# USB_SWITCH.net
KiCad netlist of a schematic drawn in Altium Designer
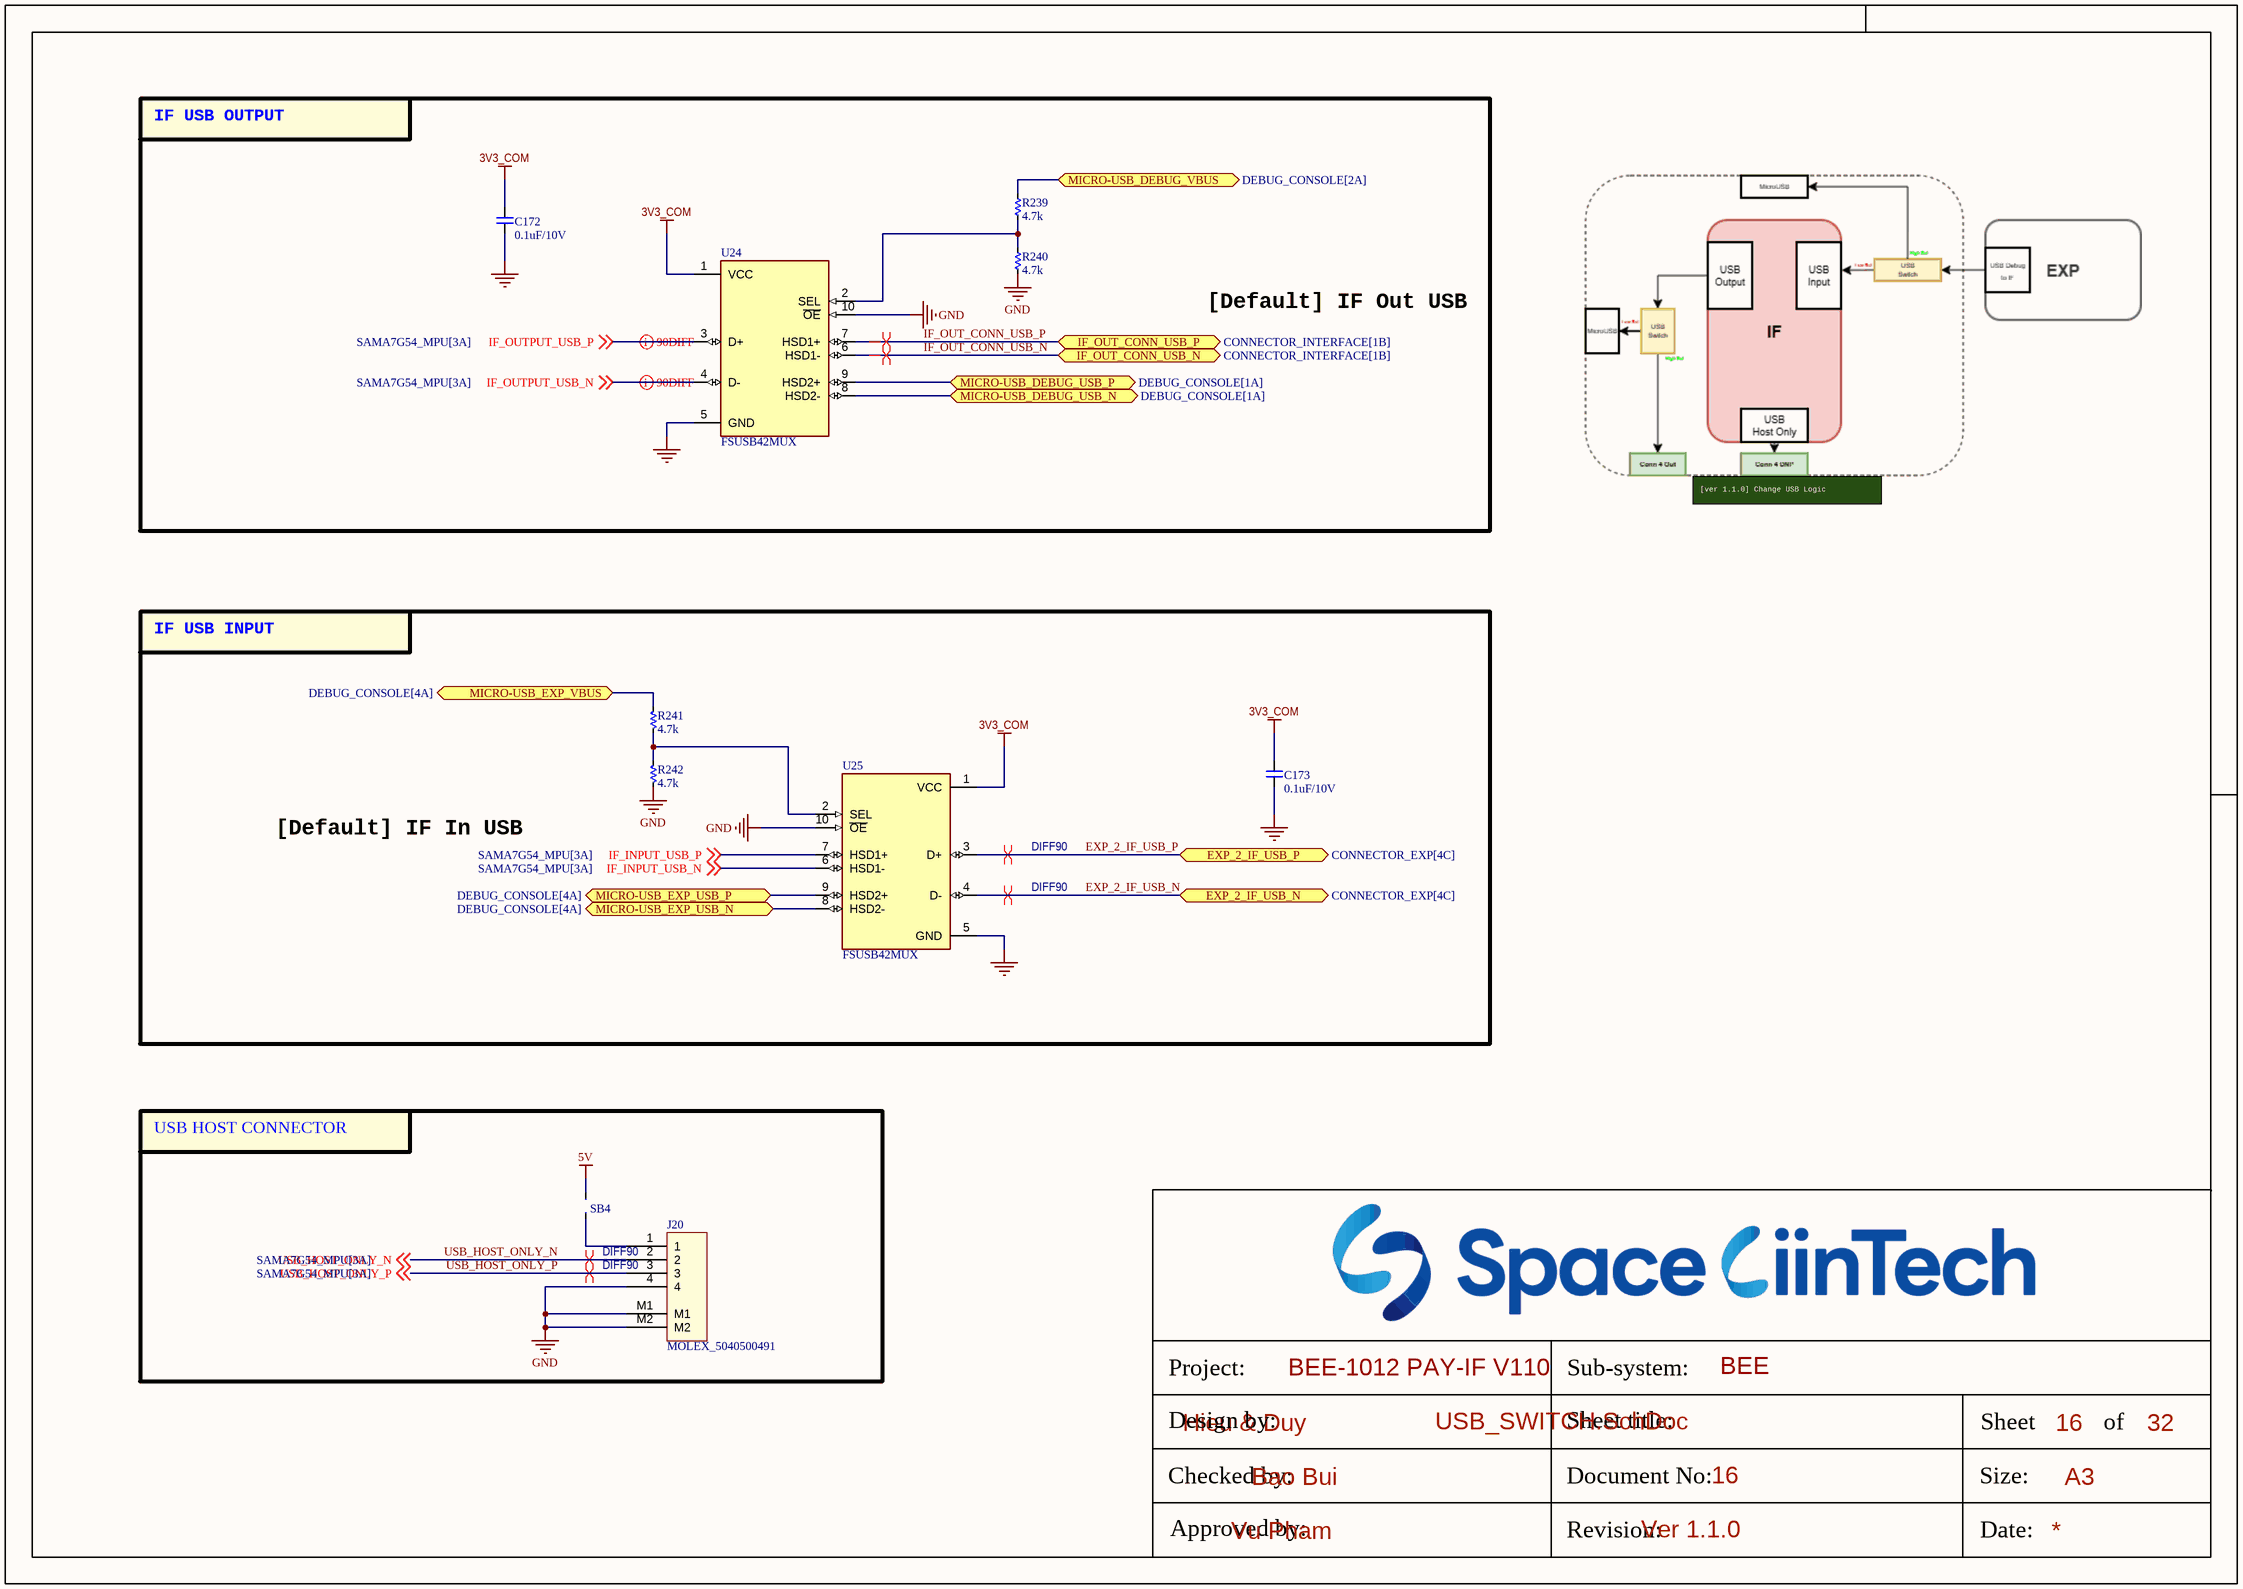
[diagram p0: USB_SWITCH.SchDoc]

(export (version "E")
  (design (tool "Eeschema 10.0.6"))
  (components
    (comp (ref "C172")
      (value "0.1uF/10V")
      (footprint "CAP_C_1005X50_L")
      (description "CAP")
      (libsource (lib "LABLIB") (part "_CAP_C_2"))
    )
    (comp (ref "C173")
      (value "0.1uF/10V")
      (footprint "CAP_C_1005X50_L")
      (description "CAP")
      (libsource (lib "LABLIB") (part "_CAP_C_2"))
    )
    (comp (ref "J20")
      (value "MOLEX_5040500491")
      (footprint "MOLEX_5040500491")
      (libsource (lib "IFBschelib") (part "Header 4x1_2M"))
    )
    (comp (ref "R239")
      (value "4.7k")
      (footprint "RES_C_1005x30_L")
      (description "RES")
      (libsource (lib "IFBschelib") (part "_RES_B_2"))
    )
    (comp (ref "R240")
      (value "4.7k")
      (footprint "RES_C_1005x30_L")
      (description "RES")
      (libsource (lib "IFBschelib") (part "_RES_B_2"))
    )
    (comp (ref "R241")
      (value "4.7k")
      (footprint "RES_C_1005x30_L")
      (description "RES")
      (libsource (lib "IFBschelib") (part "_RES_B_2"))
    )
    (comp (ref "R242")
      (value "4.7k")
      (footprint "RES_C_1005x30_L")
      (description "RES")
      (libsource (lib "IFBschelib") (part "_RES_B_2"))
    )
    (comp (ref "SB4")
      (value "JUMPER")
      (footprint "JUMPER_1608")
      (libsource (lib "IFBschelib") (part "JUMPER"))
    )
    (comp (ref "U24")
      (value "FSUSB42MUX")
      (footprint "SOP50P490X110-10N")
      (description "FSUSB42 Series DPDT 4.3 V 480 Mbps SMT Hi Speed USB 2.0 Switch - MSOP-10")
      (fields (field (name "MF") "ON Semiconductor"))
      (libsource (lib "IFBschelib") (part "FSUSB42MUX"))
    )
    (comp (ref "U25")
      (value "FSUSB42MUX")
      (footprint "SOP50P490X110-10N")
      (description "FSUSB42 Series DPDT 4.3 V 480 Mbps SMT Hi Speed USB 2.0 Switch - MSOP-10")
      (fields (field (name "MF") "ON Semiconductor"))
      (libsource (lib "") (part "FSUSB42MUX_1"))
    )
  )
  (nets
    (net (code "1") (name "/EXP_2_IF_USB_N") (class "Default")
      (node (ref "U25") (pin "4") (pinfunction "D-_4") (pintype "bidirectional"))
    )
    (net (code "2") (name "/EXP_2_IF_USB_P") (class "Default")
      (node (ref "U25") (pin "3") (pinfunction "D+_3") (pintype "bidirectional"))
    )
    (net (code "3") (name "/IF_OUT_CONN_USB_N") (class "Default")
      (node (ref "U24") (pin "6") (pinfunction "HSD1-_6") (pintype "bidirectional"))
    )
    (net (code "4") (name "/IF_OUT_CONN_USB_P") (class "Default")
      (node (ref "U24") (pin "7") (pinfunction "HSD1+_7") (pintype "bidirectional"))
    )
    (net (code "5") (name "/MICRO-USB_DEBUG_USB_N") (class "Default")
      (node (ref "U24") (pin "8") (pinfunction "HSD2-_8") (pintype "bidirectional"))
    )
    (net (code "6") (name "/MICRO-USB_DEBUG_USB_P") (class "Default")
      (node (ref "U24") (pin "9") (pinfunction "HSD2+_9") (pintype "bidirectional"))
    )
    (net (code "7") (name "/MICRO-USB_DEBUG_VBUS") (class "Default")
      (node (ref "R239") (pin "1") (pinfunction "1_1") (pintype "passive"))
    )
    (net (code "8") (name "/MICRO-USB_EXP_USB_N") (class "Default")
      (node (ref "U25") (pin "8") (pinfunction "HSD2-_8") (pintype "bidirectional"))
    )
    (net (code "9") (name "/MICRO-USB_EXP_USB_P") (class "Default")
      (node (ref "U25") (pin "9") (pinfunction "HSD2+_9") (pintype "bidirectional"))
    )
    (net (code "10") (name "/MICRO-USB_EXP_VBUS") (class "Default")
      (node (ref "R241") (pin "1") (pinfunction "1_1") (pintype "passive"))
    )
    (net (code "11") (name "3V3_COM") (class "Default")
      (node (ref "C172") (pin "2") (pinfunction "2_2") (pintype "passive"))
      (node (ref "C173") (pin "2") (pinfunction "2_2") (pintype "passive"))
      (node (ref "U24") (pin "1") (pinfunction "VCC_1") (pintype "power_in"))
      (node (ref "U25") (pin "1") (pinfunction "VCC_1") (pintype "power_in"))
    )
    (net (code "12") (name "5V") (class "Default")
      (node (ref "SB4") (pin "1") (pinfunction "1_1") (pintype "passive"))
    )
    (net (code "13") (name "GND") (class "Default")
      (node (ref "C172") (pin "1") (pinfunction "1_1") (pintype "passive"))
      (node (ref "C173") (pin "1") (pinfunction "1_1") (pintype "passive"))
      (node (ref "J20") (pin "4") (pinfunction "4_4") (pintype "passive"))
      (node (ref "J20") (pin "M1") (pinfunction "M1_M1") (pintype "passive"))
      (node (ref "J20") (pin "M2") (pinfunction "M2_M2") (pintype "passive"))
      (node (ref "R240") (pin "2") (pinfunction "2_2") (pintype "passive"))
      (node (ref "R242") (pin "2") (pinfunction "2_2") (pintype "passive"))
      (node (ref "U24") (pin "10") (pinfunction "~{OE}_10") (pintype "input"))
      (node (ref "U24") (pin "5") (pinfunction "GND_5") (pintype "power_in"))
      (node (ref "U25") (pin "10") (pinfunction "~{OE}_10") (pintype "input"))
      (node (ref "U25") (pin "5") (pinfunction "GND_5") (pintype "power_in"))
    )
    (net (code "14") (name "IF_INPUT_USB_N") (class "Default")
      (node (ref "U25") (pin "6") (pinfunction "HSD1-_6") (pintype "bidirectional"))
    )
    (net (code "15") (name "IF_INPUT_USB_P") (class "Default")
      (node (ref "U25") (pin "7") (pinfunction "HSD1+_7") (pintype "bidirectional"))
    )
    (net (code "16") (name "IF_OUTPUT_USB_N") (class "Default")
      (node (ref "U24") (pin "4") (pinfunction "D-_4") (pintype "bidirectional"))
    )
    (net (code "17") (name "IF_OUTPUT_USB_P") (class "Default")
      (node (ref "U24") (pin "3") (pinfunction "D+_3") (pintype "bidirectional"))
    )
    (net (code "18") (name "Net-(J20-Pad1)") (class "Default")
      (node (ref "J20") (pin "1") (pinfunction "1_1") (pintype "passive"))
      (node (ref "SB4") (pin "2") (pinfunction "2_2") (pintype "passive"))
    )
    (net (code "19") (name "Net-(U24-SEL)") (class "Default")
      (node (ref "R239") (pin "2") (pinfunction "2_2") (pintype "passive"))
      (node (ref "R240") (pin "1") (pinfunction "1_1") (pintype "passive"))
      (node (ref "U24") (pin "2") (pinfunction "SEL_2") (pintype "input"))
    )
    (net (code "20") (name "Net-(U25-SEL)") (class "Default")
      (node (ref "R241") (pin "2") (pinfunction "2_2") (pintype "passive"))
      (node (ref "R242") (pin "1") (pinfunction "1_1") (pintype "passive"))
      (node (ref "U25") (pin "2") (pinfunction "SEL_2") (pintype "input"))
    )
    (net (code "21") (name "USB_HOST_ONLY_N") (class "Default")
      (node (ref "J20") (pin "2") (pinfunction "2_2") (pintype "passive"))
    )
    (net (code "22") (name "USB_HOST_ONLY_P") (class "Default")
      (node (ref "J20") (pin "3") (pinfunction "3_3") (pintype "passive"))
    )
  )
)
